# Adafruit_TCS34725.net
KiCad netlist of a schematic drawn in EAGLE
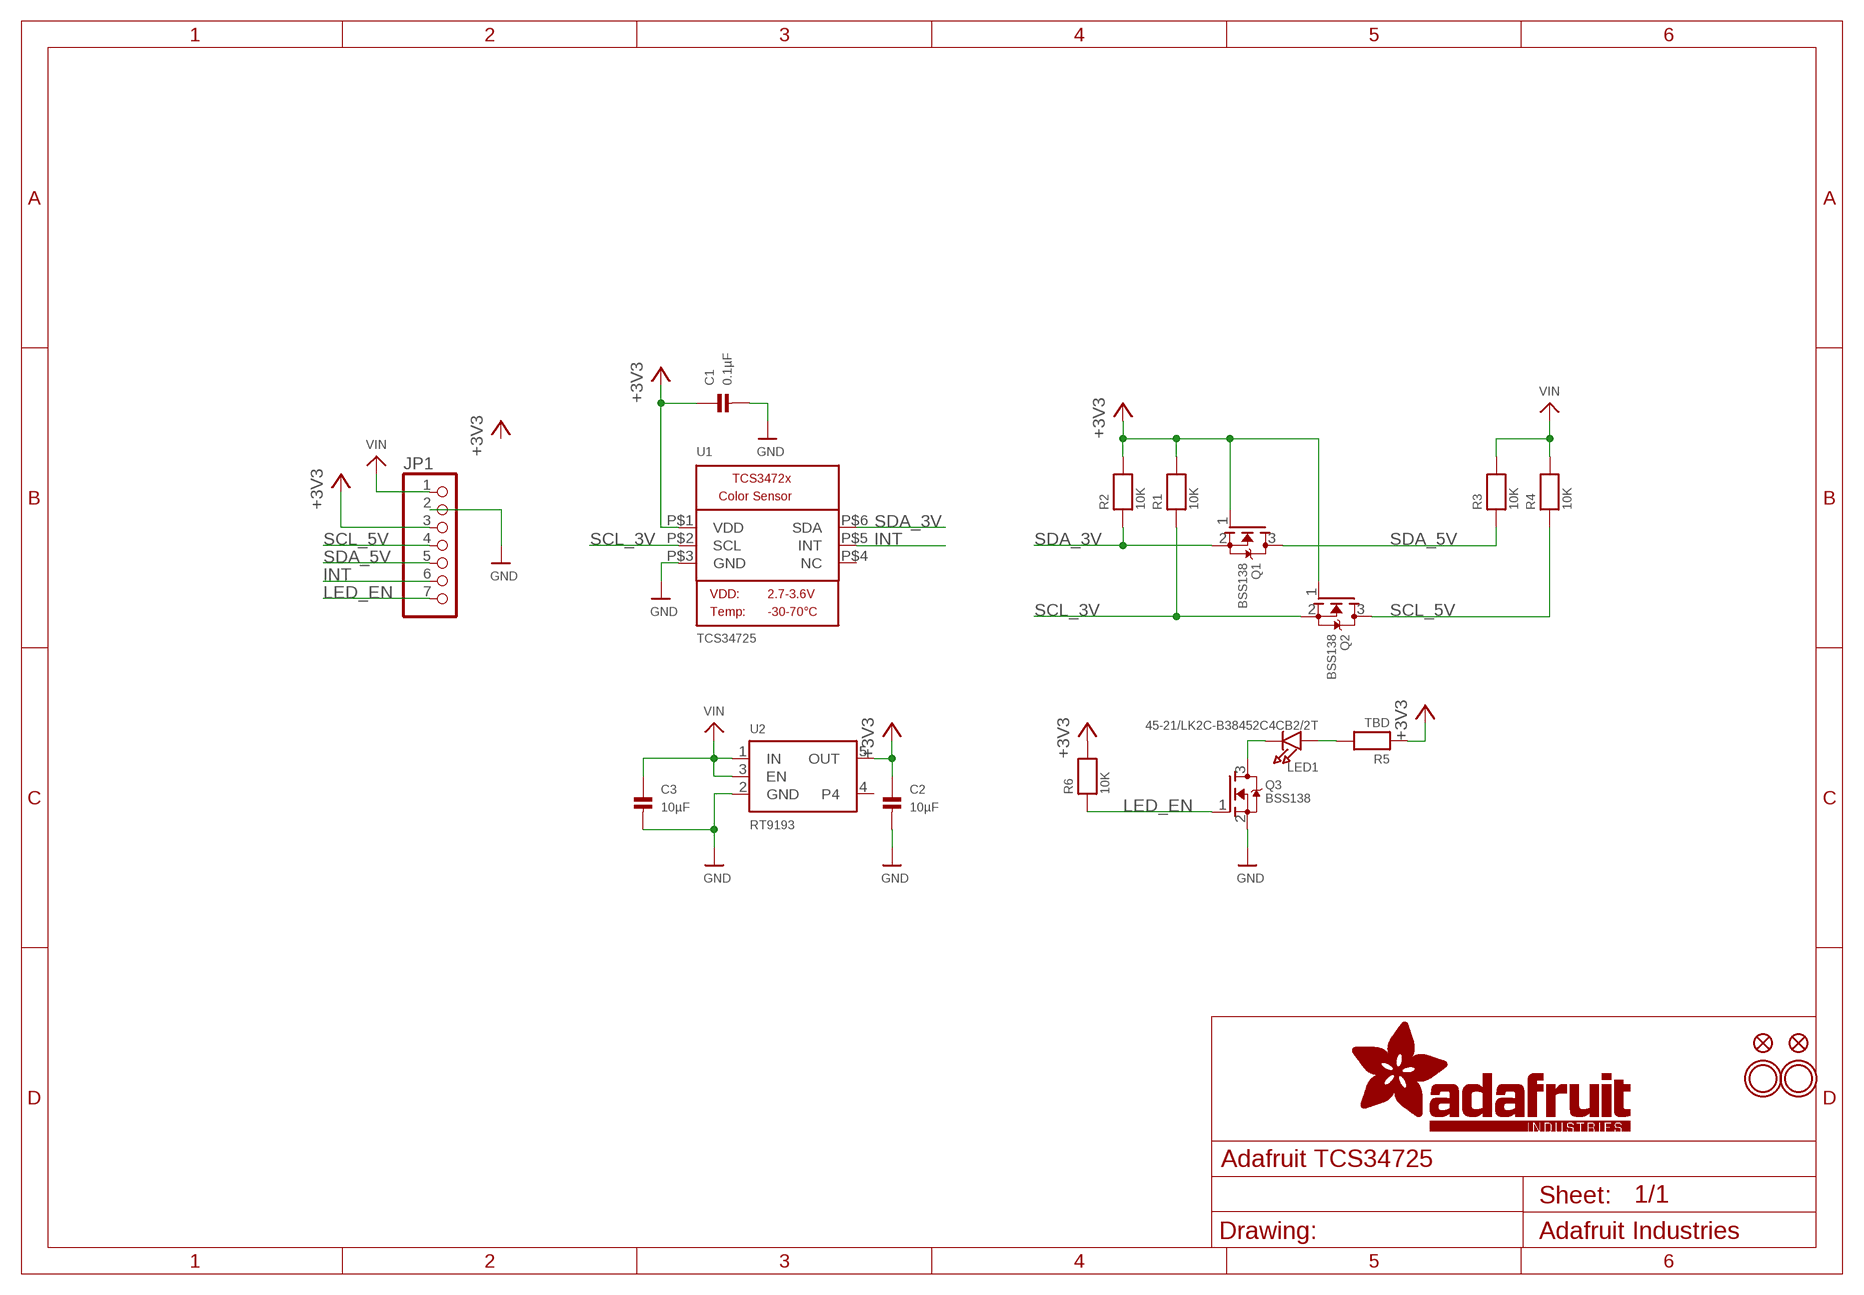
[diagram p0: schematic, sheet 1]

(export (version "E")
  (design (tool "Eeschema 10.0.6"))
  (components
    (comp (ref "C1")
      (value "0.1µF")
      (footprint "eagle-import:_0805")
      (libsource (lib "eagle-import") (part "CAP_CERAMIC_0805"))
    )
    (comp (ref "C2")
      (value "10µF")
      (footprint "eagle-import:_0805")
      (libsource (lib "eagle-import") (part "CAP_CERAMIC_0805"))
    )
    (comp (ref "C3")
      (value "10µF")
      (footprint "eagle-import:_0805")
      (libsource (lib "eagle-import") (part "CAP_CERAMIC_0805"))
    )
    (comp (ref "FID1")
      (value "FIDUCIAL\"\"")
      (footprint "eagle-import:FIDUCIAL_1MM")
      (libsource (lib "eagle-import") (part "FIDUCIAL{dblquote}{dblquote}"))
    )
    (comp (ref "FID2")
      (value "FIDUCIAL\"\"")
      (footprint "eagle-import:FIDUCIAL_1MM")
      (libsource (lib "eagle-import") (part "FIDUCIAL{dblquote}{dblquote}"))
    )
    (comp (ref "JP1")
      (value "HEADER-1X770MIL")
      (footprint "eagle-import:1X07_ROUND_70")
      (libsource (lib "eagle-import") (part "HEADER-1X770MIL"))
    )
    (comp (ref "LED1")
      (value "45-21/LK2C-B38452C4CB2/2T")
      (footprint "eagle-import:EVERLIGHT_45-21")
      (libsource (lib "eagle-import") (part "LEDEV45-21"))
    )
    (comp (ref "Q1")
      (value "BSS138")
      (footprint "eagle-import:SOT23-WIDE")
      (libsource (lib "eagle-import") (part "MOSFET-NWIDE"))
    )
    (comp (ref "Q2")
      (value "BSS138")
      (footprint "eagle-import:SOT23-WIDE")
      (libsource (lib "eagle-import") (part "MOSFET-NWIDE"))
    )
    (comp (ref "Q3")
      (value "BSS138")
      (footprint "eagle-import:SOT23-WIDE")
      (libsource (lib "eagle-import") (part "MOSFET-NWIDE"))
    )
    (comp (ref "R1")
      (value "10K")
      (footprint "eagle-import:_0805")
      (libsource (lib "eagle-import") (part "RESISTOR_0805"))
    )
    (comp (ref "R2")
      (value "10K")
      (footprint "eagle-import:_0805")
      (libsource (lib "eagle-import") (part "RESISTOR_0805"))
    )
    (comp (ref "R3")
      (value "10K")
      (footprint "eagle-import:_0805")
      (libsource (lib "eagle-import") (part "RESISTOR_0805"))
    )
    (comp (ref "R4")
      (value "10K")
      (footprint "eagle-import:_0805")
      (libsource (lib "eagle-import") (part "RESISTOR_0805"))
    )
    (comp (ref "R5")
      (value "TBD")
      (footprint "eagle-import:_0805")
      (libsource (lib "eagle-import") (part "RESISTOR_0805"))
    )
    (comp (ref "R6")
      (value "10K")
      (footprint "eagle-import:_0805")
      (libsource (lib "eagle-import") (part "RESISTOR_0805"))
    )
    (comp (ref "U$8")
      (value "MOUNTINGHOLE2.5")
      (footprint "eagle-import:MOUNTINGHOLE_2.5_PLATED")
      (libsource (lib "eagle-import") (part "MOUNTINGHOLE2.5"))
    )
    (comp (ref "U$14")
      (value "MOUNTINGHOLE2.5")
      (footprint "eagle-import:MOUNTINGHOLE_2.5_PLATED")
      (libsource (lib "eagle-import") (part "MOUNTINGHOLE2.5"))
    )
    (comp (ref "U1")
      (value "TCS34725")
      (footprint "eagle-import:TCS3472_FN6")
      (libsource (lib "eagle-import") (part "LIGHT_TCS3472"))
    )
    (comp (ref "U2")
      (value "RT9193")
      (footprint "eagle-import:SOT23-5")
      (libsource (lib "eagle-import") (part "VREG_SOT23-5"))
    )
  )
  (nets
    (net (code "1") (name "+3V3") (class "Default")
      (node (ref "C1") (pin "1") (pinfunction "P$1_1") (pintype "passive"))
      (node (ref "C2") (pin "1") (pinfunction "P$1_1") (pintype "passive"))
      (node (ref "JP1") (pin "3") (pinfunction "3_3") (pintype "passive"))
      (node (ref "Q1") (pin "1") (pinfunction "G_1") (pintype "bidirectional"))
      (node (ref "Q2") (pin "1") (pinfunction "G_1") (pintype "bidirectional"))
      (node (ref "R1") (pin "2") (pinfunction "2_2") (pintype "passive"))
      (node (ref "R2") (pin "2") (pinfunction "2_2") (pintype "passive"))
      (node (ref "R5") (pin "1") (pinfunction "1_1") (pintype "passive"))
      (node (ref "R6") (pin "2") (pinfunction "2_2") (pintype "passive"))
      (node (ref "U1") (pin "P$1") (pinfunction "VDD_P$1") (pintype "power_in"))
      (node (ref "U2") (pin "5") (pinfunction "OUT_5") (pintype "bidirectional"))
    )
    (net (code "2") (name "/INT") (class "Default")
      (node (ref "JP1") (pin "6") (pinfunction "6_6") (pintype "passive"))
      (node (ref "U1") (pin "P$5") (pinfunction "INT_P$5") (pintype "output"))
    )
    (net (code "3") (name "/LED_EN") (class "Default")
      (node (ref "JP1") (pin "7") (pinfunction "7_7") (pintype "passive"))
      (node (ref "Q3") (pin "1") (pinfunction "G_1") (pintype "bidirectional"))
      (node (ref "R6") (pin "1") (pinfunction "1_1") (pintype "passive"))
    )
    (net (code "4") (name "/SCL_3V") (class "Default")
      (node (ref "Q2") (pin "2") (pinfunction "S_2") (pintype "bidirectional"))
      (node (ref "R1") (pin "1") (pinfunction "1_1") (pintype "passive"))
      (node (ref "U1") (pin "P$2") (pinfunction "SCL_P$2") (pintype "bidirectional"))
    )
    (net (code "5") (name "/SCL_5V") (class "Default")
      (node (ref "JP1") (pin "4") (pinfunction "4_4") (pintype "passive"))
      (node (ref "Q2") (pin "3") (pinfunction "D_3") (pintype "bidirectional"))
      (node (ref "R4") (pin "1") (pinfunction "1_1") (pintype "passive"))
    )
    (net (code "6") (name "/SDA_3V") (class "Default")
      (node (ref "Q1") (pin "2") (pinfunction "S_2") (pintype "bidirectional"))
      (node (ref "R2") (pin "1") (pinfunction "1_1") (pintype "passive"))
      (node (ref "U1") (pin "P$6") (pinfunction "SDA_P$6") (pintype "bidirectional"))
    )
    (net (code "7") (name "/SDA_5V") (class "Default")
      (node (ref "JP1") (pin "5") (pinfunction "5_5") (pintype "passive"))
      (node (ref "Q1") (pin "3") (pinfunction "D_3") (pintype "bidirectional"))
      (node (ref "R3") (pin "1") (pinfunction "1_1") (pintype "passive"))
    )
    (net (code "8") (name "GND") (class "Default")
      (node (ref "C1") (pin "2") (pinfunction "P$2_2") (pintype "passive"))
      (node (ref "C2") (pin "2") (pinfunction "P$2_2") (pintype "passive"))
      (node (ref "C3") (pin "2") (pinfunction "P$2_2") (pintype "passive"))
      (node (ref "JP1") (pin "2") (pinfunction "2_2") (pintype "passive"))
      (node (ref "Q3") (pin "2") (pinfunction "S_2") (pintype "bidirectional"))
      (node (ref "U1") (pin "P$3") (pinfunction "GND_P$3") (pintype "power_in"))
      (node (ref "U2") (pin "2") (pinfunction "GND_2") (pintype "bidirectional"))
    )
    (net (code "9") (name "Net-(LED1-C)") (class "Default")
      (node (ref "LED1") (pin "K") (pinfunction "C_K") (pintype "passive"))
      (node (ref "Q3") (pin "3") (pinfunction "D_3") (pintype "bidirectional"))
    )
    (net (code "10") (name "Net-(LED1-PadA)") (class "Default")
      (node (ref "LED1") (pin "A") (pinfunction "A_A") (pintype "passive"))
      (node (ref "R5") (pin "2") (pinfunction "2_2") (pintype "passive"))
    )
    (net (code "11") (name "VIN") (class "Default")
      (node (ref "C3") (pin "1") (pinfunction "P$1_1") (pintype "passive"))
      (node (ref "JP1") (pin "1") (pinfunction "1_1") (pintype "passive"))
      (node (ref "R3") (pin "2") (pinfunction "2_2") (pintype "passive"))
      (node (ref "R4") (pin "2") (pinfunction "2_2") (pintype "passive"))
      (node (ref "U2") (pin "1") (pinfunction "IN_1") (pintype "bidirectional"))
      (node (ref "U2") (pin "3") (pinfunction "EN_3") (pintype "bidirectional"))
    )
    (net (code "12") (name "unconnected-(U1-NC-PadP$4)") (class "Default")
      (node (ref "U1") (pin "P$4") (pinfunction "NC_P$4") (pintype "no_connect"))
    )
    (net (code "13") (name "unconnected-(U2-P4-Pad4)") (class "Default")
      (node (ref "U2") (pin "4") (pinfunction "P4_4") (pintype "bidirectional"))
    )
  )
)
